# design.net
KiCad netlist of a schematic drawn in Altium Designer
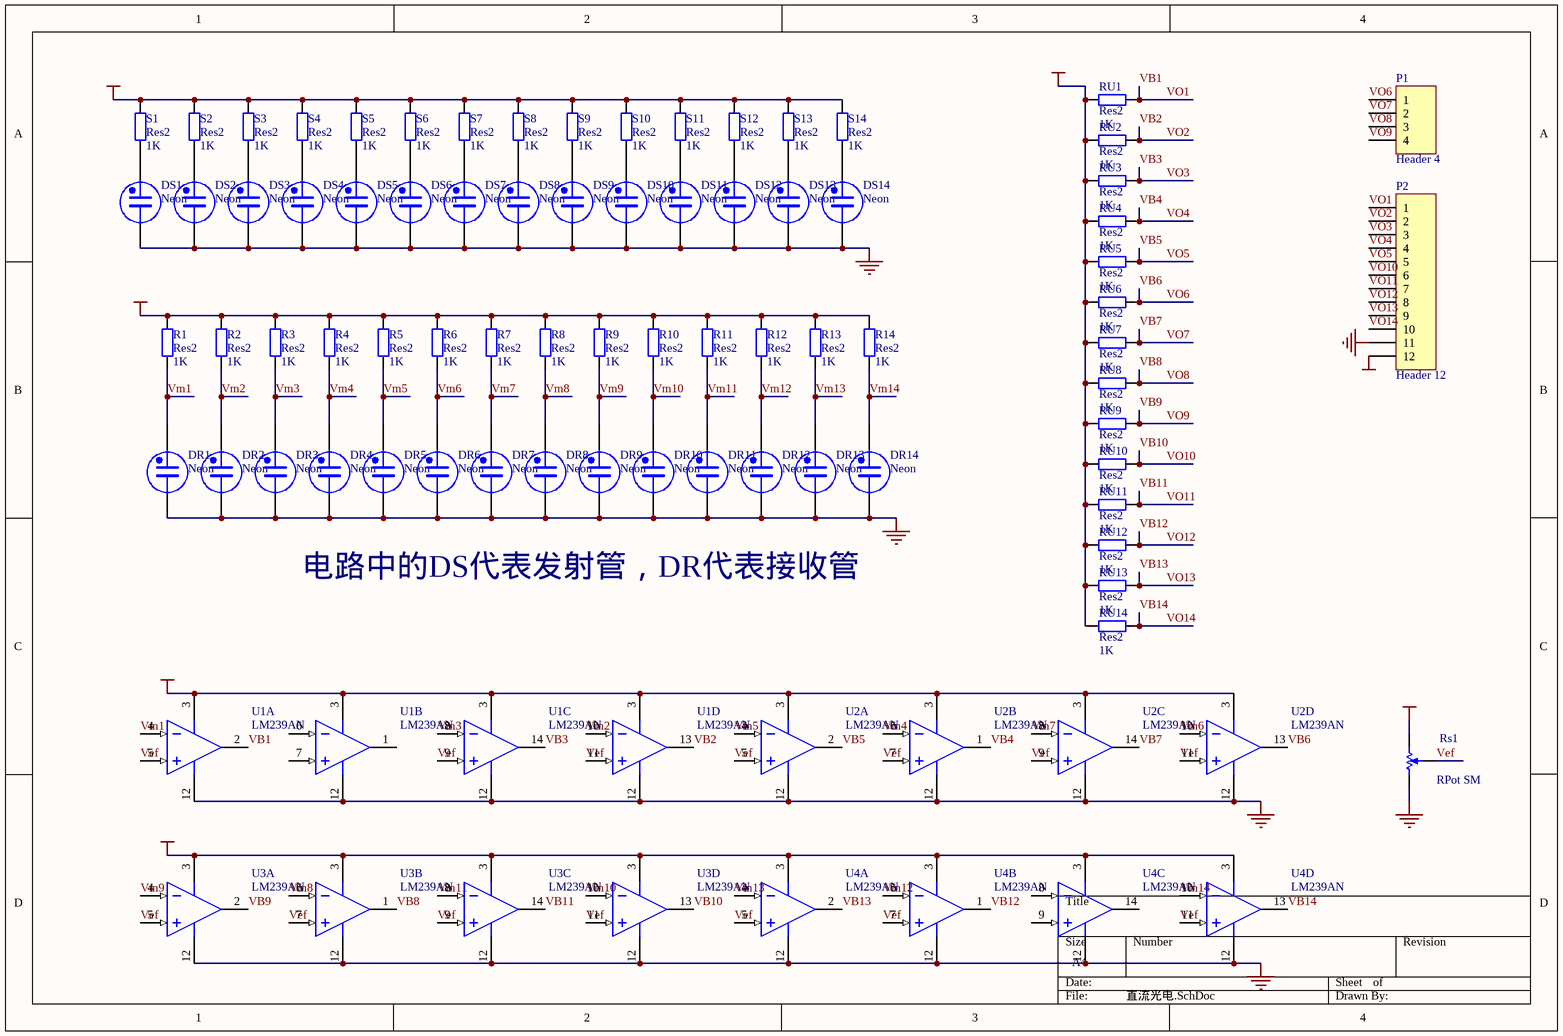
[diagram p0: 直流光电.SchDoc]

(export (version "E")
  (design (tool "Eeschema 10.0.6"))
  (components
    (comp (ref "DR1")
      (value "Neon")
      (footprint "PIN2")
      (description "Neon Bulb")
      (fields (field (name "PUBLISHER") "Altium Limited"))
      (libsource (lib "Miscellaneous Devices") (part "Neon"))
    )
    (comp (ref "DR2")
      (value "Neon")
      (footprint "PIN2")
      (description "Neon Bulb")
      (fields (field (name "PUBLISHER") "Altium Limited"))
      (libsource (lib "Miscellaneous Devices") (part "Neon"))
    )
    (comp (ref "DR3")
      (value "Neon")
      (footprint "PIN2")
      (description "Neon Bulb")
      (fields (field (name "PUBLISHER") "Altium Limited"))
      (libsource (lib "Miscellaneous Devices") (part "Neon"))
    )
    (comp (ref "DR4")
      (value "Neon")
      (footprint "PIN2")
      (description "Neon Bulb")
      (fields (field (name "PUBLISHER") "Altium Limited"))
      (libsource (lib "Miscellaneous Devices") (part "Neon"))
    )
    (comp (ref "DR5")
      (value "Neon")
      (footprint "PIN2")
      (description "Neon Bulb")
      (fields (field (name "PUBLISHER") "Altium Limited"))
      (libsource (lib "Miscellaneous Devices") (part "Neon"))
    )
    (comp (ref "DR6")
      (value "Neon")
      (footprint "PIN2")
      (description "Neon Bulb")
      (fields (field (name "PUBLISHER") "Altium Limited"))
      (libsource (lib "Miscellaneous Devices") (part "Neon"))
    )
    (comp (ref "DR7")
      (value "Neon")
      (footprint "PIN2")
      (description "Neon Bulb")
      (fields (field (name "PUBLISHER") "Altium Limited"))
      (libsource (lib "Miscellaneous Devices") (part "Neon"))
    )
    (comp (ref "DR8")
      (value "Neon")
      (footprint "PIN2")
      (description "Neon Bulb")
      (fields (field (name "PUBLISHER") "Altium Limited"))
      (libsource (lib "Miscellaneous Devices") (part "Neon"))
    )
    (comp (ref "DR9")
      (value "Neon")
      (footprint "PIN2")
      (description "Neon Bulb")
      (fields (field (name "PUBLISHER") "Altium Limited"))
      (libsource (lib "Miscellaneous Devices") (part "Neon"))
    )
    (comp (ref "DR10")
      (value "Neon")
      (footprint "PIN2")
      (description "Neon Bulb")
      (fields (field (name "PUBLISHER") "Altium Limited"))
      (libsource (lib "Miscellaneous Devices") (part "Neon"))
    )
    (comp (ref "DR11")
      (value "Neon")
      (footprint "PIN2")
      (description "Neon Bulb")
      (fields (field (name "PUBLISHER") "Altium Limited"))
      (libsource (lib "Miscellaneous Devices") (part "Neon"))
    )
    (comp (ref "DR12")
      (value "Neon")
      (footprint "PIN2")
      (description "Neon Bulb")
      (fields (field (name "PUBLISHER") "Altium Limited"))
      (libsource (lib "Miscellaneous Devices") (part "Neon"))
    )
    (comp (ref "DR13")
      (value "Neon")
      (footprint "PIN2")
      (description "Neon Bulb")
      (fields (field (name "PUBLISHER") "Altium Limited"))
      (libsource (lib "Miscellaneous Devices") (part "Neon"))
    )
    (comp (ref "DR14")
      (value "Neon")
      (footprint "PIN2")
      (description "Neon Bulb")
      (fields (field (name "PUBLISHER") "Altium Limited"))
      (libsource (lib "Miscellaneous Devices") (part "Neon"))
    )
    (comp (ref "DS1")
      (value "Neon")
      (footprint "PIN2")
      (description "Neon Bulb")
      (fields (field (name "PUBLISHER") "Altium Limited"))
      (libsource (lib "Miscellaneous Devices") (part "Neon"))
    )
    (comp (ref "DS2")
      (value "Neon")
      (footprint "PIN2")
      (description "Neon Bulb")
      (fields (field (name "PUBLISHER") "Altium Limited"))
      (libsource (lib "Miscellaneous Devices") (part "Neon"))
    )
    (comp (ref "DS3")
      (value "Neon")
      (footprint "PIN2")
      (description "Neon Bulb")
      (fields (field (name "PUBLISHER") "Altium Limited"))
      (libsource (lib "Miscellaneous Devices") (part "Neon"))
    )
    (comp (ref "DS4")
      (value "Neon")
      (footprint "PIN2")
      (description "Neon Bulb")
      (fields (field (name "PUBLISHER") "Altium Limited"))
      (libsource (lib "Miscellaneous Devices") (part "Neon"))
    )
    (comp (ref "DS5")
      (value "Neon")
      (footprint "PIN2")
      (description "Neon Bulb")
      (fields (field (name "PUBLISHER") "Altium Limited"))
      (libsource (lib "Miscellaneous Devices") (part "Neon"))
    )
    (comp (ref "DS6")
      (value "Neon")
      (footprint "PIN2")
      (description "Neon Bulb")
      (fields (field (name "PUBLISHER") "Altium Limited"))
      (libsource (lib "Miscellaneous Devices") (part "Neon"))
    )
    (comp (ref "DS7")
      (value "Neon")
      (footprint "PIN2")
      (description "Neon Bulb")
      (fields (field (name "PUBLISHER") "Altium Limited"))
      (libsource (lib "Miscellaneous Devices") (part "Neon"))
    )
    (comp (ref "DS8")
      (value "Neon")
      (footprint "PIN2")
      (description "Neon Bulb")
      (fields (field (name "PUBLISHER") "Altium Limited"))
      (libsource (lib "Miscellaneous Devices") (part "Neon"))
    )
    (comp (ref "DS9")
      (value "Neon")
      (footprint "PIN2")
      (description "Neon Bulb")
      (fields (field (name "PUBLISHER") "Altium Limited"))
      (libsource (lib "Miscellaneous Devices") (part "Neon"))
    )
    (comp (ref "DS10")
      (value "Neon")
      (footprint "PIN2")
      (description "Neon Bulb")
      (fields (field (name "PUBLISHER") "Altium Limited"))
      (libsource (lib "Miscellaneous Devices") (part "Neon"))
    )
    (comp (ref "DS11")
      (value "Neon")
      (footprint "PIN2")
      (description "Neon Bulb")
      (fields (field (name "PUBLISHER") "Altium Limited"))
      (libsource (lib "Miscellaneous Devices") (part "Neon"))
    )
    (comp (ref "DS12")
      (value "Neon")
      (footprint "PIN2")
      (description "Neon Bulb")
      (fields (field (name "PUBLISHER") "Altium Limited"))
      (libsource (lib "Miscellaneous Devices") (part "Neon"))
    )
    (comp (ref "DS13")
      (value "Neon")
      (footprint "PIN2")
      (description "Neon Bulb")
      (fields (field (name "PUBLISHER") "Altium Limited"))
      (libsource (lib "Miscellaneous Devices") (part "Neon"))
    )
    (comp (ref "DS14")
      (value "Neon")
      (footprint "PIN2")
      (description "Neon Bulb")
      (fields (field (name "PUBLISHER") "Altium Limited"))
      (libsource (lib "Miscellaneous Devices") (part "Neon"))
    )
    (comp (ref "P1")
      (value "Header 4")
      (footprint "HDR1X4")
      (description "Header, 4-Pin")
      (fields (field (name "PUBLISHER") "Altium Limited"))
      (libsource (lib "Miscellaneous Connectors") (part "Header 4"))
    )
    (comp (ref "P2")
      (value "Header 12")
      (footprint "HDR1X12")
      (description "Header, 12-Pin")
      (fields (field (name "PUBLISHER") "Altium Limited"))
      (libsource (lib "Miscellaneous Connectors") (part "Header 12"))
    )
    (comp (ref "R1")
      (value "Res2")
      (footprint "AXIAL-0.4")
      (description "Resistor")
      (fields (field (name "ALTIUM_VALUE") "1K") (field (name "PUBLISHER") "Altium Limited"))
      (libsource (lib "Miscellaneous Devices") (part "Res2"))
    )
    (comp (ref "R2")
      (value "Res2")
      (footprint "AXIAL-0.4")
      (description "Resistor")
      (fields (field (name "ALTIUM_VALUE") "1K") (field (name "PUBLISHER") "Altium Limited"))
      (libsource (lib "Miscellaneous Devices") (part "Res2"))
    )
    (comp (ref "R3")
      (value "Res2")
      (footprint "AXIAL-0.4")
      (description "Resistor")
      (fields (field (name "ALTIUM_VALUE") "1K") (field (name "PUBLISHER") "Altium Limited"))
      (libsource (lib "Miscellaneous Devices") (part "Res2"))
    )
    (comp (ref "R4")
      (value "Res2")
      (footprint "AXIAL-0.4")
      (description "Resistor")
      (fields (field (name "ALTIUM_VALUE") "1K") (field (name "PUBLISHER") "Altium Limited"))
      (libsource (lib "Miscellaneous Devices") (part "Res2"))
    )
    (comp (ref "R5")
      (value "Res2")
      (footprint "AXIAL-0.4")
      (description "Resistor")
      (fields (field (name "ALTIUM_VALUE") "1K") (field (name "PUBLISHER") "Altium Limited"))
      (libsource (lib "Miscellaneous Devices") (part "Res2"))
    )
    (comp (ref "R6")
      (value "Res2")
      (footprint "AXIAL-0.4")
      (description "Resistor")
      (fields (field (name "ALTIUM_VALUE") "1K") (field (name "PUBLISHER") "Altium Limited"))
      (libsource (lib "Miscellaneous Devices") (part "Res2"))
    )
    (comp (ref "R7")
      (value "Res2")
      (footprint "AXIAL-0.4")
      (description "Resistor")
      (fields (field (name "ALTIUM_VALUE") "1K") (field (name "PUBLISHER") "Altium Limited"))
      (libsource (lib "Miscellaneous Devices") (part "Res2"))
    )
    (comp (ref "R8")
      (value "Res2")
      (footprint "AXIAL-0.4")
      (description "Resistor")
      (fields (field (name "ALTIUM_VALUE") "1K") (field (name "PUBLISHER") "Altium Limited"))
      (libsource (lib "Miscellaneous Devices") (part "Res2"))
    )
    (comp (ref "R9")
      (value "Res2")
      (footprint "AXIAL-0.4")
      (description "Resistor")
      (fields (field (name "ALTIUM_VALUE") "1K") (field (name "PUBLISHER") "Altium Limited"))
      (libsource (lib "Miscellaneous Devices") (part "Res2"))
    )
    (comp (ref "R10")
      (value "Res2")
      (footprint "AXIAL-0.4")
      (description "Resistor")
      (fields (field (name "ALTIUM_VALUE") "1K") (field (name "PUBLISHER") "Altium Limited"))
      (libsource (lib "Miscellaneous Devices") (part "Res2"))
    )
    (comp (ref "R11")
      (value "Res2")
      (footprint "AXIAL-0.4")
      (description "Resistor")
      (fields (field (name "ALTIUM_VALUE") "1K") (field (name "PUBLISHER") "Altium Limited"))
      (libsource (lib "Miscellaneous Devices") (part "Res2"))
    )
    (comp (ref "R12")
      (value "Res2")
      (footprint "AXIAL-0.4")
      (description "Resistor")
      (fields (field (name "ALTIUM_VALUE") "1K") (field (name "PUBLISHER") "Altium Limited"))
      (libsource (lib "Miscellaneous Devices") (part "Res2"))
    )
    (comp (ref "R13")
      (value "Res2")
      (footprint "AXIAL-0.4")
      (description "Resistor")
      (fields (field (name "ALTIUM_VALUE") "1K") (field (name "PUBLISHER") "Altium Limited"))
      (libsource (lib "Miscellaneous Devices") (part "Res2"))
    )
    (comp (ref "R14")
      (value "Res2")
      (footprint "AXIAL-0.4")
      (description "Resistor")
      (fields (field (name "ALTIUM_VALUE") "1K") (field (name "PUBLISHER") "Altium Limited"))
      (libsource (lib "Miscellaneous Devices") (part "Res2"))
    )
    (comp (ref "Rs1")
      (value "RPot SM")
      (footprint "POT4MM-2")
      (description "Square Trimming Potentiometer")
      (fields (field (name "PUBLISHER") "Altium Limited"))
      (libsource (lib "Miscellaneous Devices") (part "RPot SM"))
    )
    (comp (ref "RU1")
      (value "Res2")
      (footprint "AXIAL-0.4")
      (description "Resistor")
      (fields (field (name "ALTIUM_VALUE") "1K") (field (name "PUBLISHER") "Altium Limited"))
      (libsource (lib "") (part "Res2_1"))
    )
    (comp (ref "RU2")
      (value "Res2")
      (footprint "AXIAL-0.4")
      (description "Resistor")
      (fields (field (name "ALTIUM_VALUE") "1K") (field (name "PUBLISHER") "Altium Limited"))
      (libsource (lib "") (part "Res2_1"))
    )
    (comp (ref "RU3")
      (value "Res2")
      (footprint "AXIAL-0.4")
      (description "Resistor")
      (fields (field (name "ALTIUM_VALUE") "1K") (field (name "PUBLISHER") "Altium Limited"))
      (libsource (lib "") (part "Res2_1"))
    )
    (comp (ref "RU4")
      (value "Res2")
      (footprint "AXIAL-0.4")
      (description "Resistor")
      (fields (field (name "ALTIUM_VALUE") "1K") (field (name "PUBLISHER") "Altium Limited"))
      (libsource (lib "") (part "Res2_1"))
    )
    (comp (ref "RU5")
      (value "Res2")
      (footprint "AXIAL-0.4")
      (description "Resistor")
      (fields (field (name "ALTIUM_VALUE") "1K") (field (name "PUBLISHER") "Altium Limited"))
      (libsource (lib "") (part "Res2_1"))
    )
    (comp (ref "RU6")
      (value "Res2")
      (footprint "AXIAL-0.4")
      (description "Resistor")
      (fields (field (name "ALTIUM_VALUE") "1K") (field (name "PUBLISHER") "Altium Limited"))
      (libsource (lib "") (part "Res2_1"))
    )
    (comp (ref "RU7")
      (value "Res2")
      (footprint "AXIAL-0.4")
      (description "Resistor")
      (fields (field (name "ALTIUM_VALUE") "1K") (field (name "PUBLISHER") "Altium Limited"))
      (libsource (lib "") (part "Res2_1"))
    )
    (comp (ref "RU8")
      (value "Res2")
      (footprint "AXIAL-0.4")
      (description "Resistor")
      (fields (field (name "ALTIUM_VALUE") "1K") (field (name "PUBLISHER") "Altium Limited"))
      (libsource (lib "") (part "Res2_1"))
    )
    (comp (ref "RU9")
      (value "Res2")
      (footprint "AXIAL-0.4")
      (description "Resistor")
      (fields (field (name "ALTIUM_VALUE") "1K") (field (name "PUBLISHER") "Altium Limited"))
      (libsource (lib "") (part "Res2_1"))
    )
    (comp (ref "RU10")
      (value "Res2")
      (footprint "AXIAL-0.4")
      (description "Resistor")
      (fields (field (name "ALTIUM_VALUE") "1K") (field (name "PUBLISHER") "Altium Limited"))
      (libsource (lib "") (part "Res2_1"))
    )
    (comp (ref "RU11")
      (value "Res2")
      (footprint "AXIAL-0.4")
      (description "Resistor")
      (fields (field (name "ALTIUM_VALUE") "1K") (field (name "PUBLISHER") "Altium Limited"))
      (libsource (lib "") (part "Res2_1"))
    )
    (comp (ref "RU12")
      (value "Res2")
      (footprint "AXIAL-0.4")
      (description "Resistor")
      (fields (field (name "ALTIUM_VALUE") "1K") (field (name "PUBLISHER") "Altium Limited"))
      (libsource (lib "") (part "Res2_1"))
    )
    (comp (ref "RU13")
      (value "Res2")
      (footprint "AXIAL-0.4")
      (description "Resistor")
      (fields (field (name "ALTIUM_VALUE") "1K") (field (name "PUBLISHER") "Altium Limited"))
      (libsource (lib "") (part "Res2_1"))
    )
    (comp (ref "RU14")
      (value "Res2")
      (footprint "AXIAL-0.4")
      (description "Resistor")
      (fields (field (name "ALTIUM_VALUE") "1K") (field (name "PUBLISHER") "Altium Limited"))
      (libsource (lib "") (part "Res2_1"))
    )
    (comp (ref "S1")
      (value "Res2")
      (footprint "AXIAL-0.4")
      (description "Resistor")
      (fields (field (name "ALTIUM_VALUE") "1K") (field (name "PUBLISHER") "Altium Limited"))
      (libsource (lib "Miscellaneous Devices") (part "Res2"))
    )
    (comp (ref "S2")
      (value "Res2")
      (footprint "AXIAL-0.4")
      (description "Resistor")
      (fields (field (name "ALTIUM_VALUE") "1K") (field (name "PUBLISHER") "Altium Limited"))
      (libsource (lib "Miscellaneous Devices") (part "Res2"))
    )
    (comp (ref "S3")
      (value "Res2")
      (footprint "AXIAL-0.4")
      (description "Resistor")
      (fields (field (name "ALTIUM_VALUE") "1K") (field (name "PUBLISHER") "Altium Limited"))
      (libsource (lib "Miscellaneous Devices") (part "Res2"))
    )
    (comp (ref "S4")
      (value "Res2")
      (footprint "AXIAL-0.4")
      (description "Resistor")
      (fields (field (name "ALTIUM_VALUE") "1K") (field (name "PUBLISHER") "Altium Limited"))
      (libsource (lib "Miscellaneous Devices") (part "Res2"))
    )
    (comp (ref "S5")
      (value "Res2")
      (footprint "AXIAL-0.4")
      (description "Resistor")
      (fields (field (name "ALTIUM_VALUE") "1K") (field (name "PUBLISHER") "Altium Limited"))
      (libsource (lib "Miscellaneous Devices") (part "Res2"))
    )
    (comp (ref "S6")
      (value "Res2")
      (footprint "AXIAL-0.4")
      (description "Resistor")
      (fields (field (name "ALTIUM_VALUE") "1K") (field (name "PUBLISHER") "Altium Limited"))
      (libsource (lib "Miscellaneous Devices") (part "Res2"))
    )
    (comp (ref "S7")
      (value "Res2")
      (footprint "AXIAL-0.4")
      (description "Resistor")
      (fields (field (name "ALTIUM_VALUE") "1K") (field (name "PUBLISHER") "Altium Limited"))
      (libsource (lib "Miscellaneous Devices") (part "Res2"))
    )
    (comp (ref "S8")
      (value "Res2")
      (footprint "AXIAL-0.4")
      (description "Resistor")
      (fields (field (name "ALTIUM_VALUE") "1K") (field (name "PUBLISHER") "Altium Limited"))
      (libsource (lib "Miscellaneous Devices") (part "Res2"))
    )
    (comp (ref "S9")
      (value "Res2")
      (footprint "AXIAL-0.4")
      (description "Resistor")
      (fields (field (name "ALTIUM_VALUE") "1K") (field (name "PUBLISHER") "Altium Limited"))
      (libsource (lib "Miscellaneous Devices") (part "Res2"))
    )
    (comp (ref "S10")
      (value "Res2")
      (footprint "AXIAL-0.4")
      (description "Resistor")
      (fields (field (name "ALTIUM_VALUE") "1K") (field (name "PUBLISHER") "Altium Limited"))
      (libsource (lib "Miscellaneous Devices") (part "Res2"))
    )
    (comp (ref "S11")
      (value "Res2")
      (footprint "AXIAL-0.4")
      (description "Resistor")
      (fields (field (name "ALTIUM_VALUE") "1K") (field (name "PUBLISHER") "Altium Limited"))
      (libsource (lib "Miscellaneous Devices") (part "Res2"))
    )
    (comp (ref "S12")
      (value "Res2")
      (footprint "AXIAL-0.4")
      (description "Resistor")
      (fields (field (name "ALTIUM_VALUE") "1K") (field (name "PUBLISHER") "Altium Limited"))
      (libsource (lib "Miscellaneous Devices") (part "Res2"))
    )
    (comp (ref "S13")
      (value "Res2")
      (footprint "AXIAL-0.4")
      (description "Resistor")
      (fields (field (name "ALTIUM_VALUE") "1K") (field (name "PUBLISHER") "Altium Limited"))
      (libsource (lib "Miscellaneous Devices") (part "Res2"))
    )
    (comp (ref "S14")
      (value "Res2")
      (footprint "AXIAL-0.4")
      (description "Resistor")
      (fields (field (name "ALTIUM_VALUE") "1K") (field (name "PUBLISHER") "Altium Limited"))
      (libsource (lib "Miscellaneous Devices") (part "Res2"))
    )
    (comp (ref "U1")
      (value "LM239AN")
      (footprint "DIP14")
      (description "Low-Power Quad Voltage Comparator")
      (fields (field (name "PUBLISHER") "Altium Limited"))
      (libsource (lib "ST Analog Comparator") (part "LM239AN"))
    )
    (comp (ref "U2")
      (value "LM239AN")
      (footprint "DIP14")
      (description "Low-Power Quad Voltage Comparator")
      (fields (field (name "PUBLISHER") "Altium Limited"))
      (libsource (lib "ST Analog Comparator") (part "LM239AN"))
    )
    (comp (ref "U3")
      (value "LM239AN")
      (footprint "DIP14")
      (description "Low-Power Quad Voltage Comparator")
      (fields (field (name "PUBLISHER") "Altium Limited"))
      (libsource (lib "ST Analog Comparator") (part "LM239AN"))
    )
    (comp (ref "U4")
      (value "LM239AN")
      (footprint "DIP14")
      (description "Low-Power Quad Voltage Comparator")
      (fields (field (name "PUBLISHER") "Altium Limited"))
      (libsource (lib "ST Analog Comparator") (part "LM239AN"))
    )
  )
  (nets
    (net (code "1") (name "/VB1") (class "Default")
      (node (ref "P2") (pin "1") (pinfunction "1_1") (pintype "passive"))
      (node (ref "RU1") (pin "2") (pinfunction "2_2") (pintype "passive"))
      (node (ref "U1") (pin "2") (pinfunction "OUT_2") (pintype "open_collector"))
    )
    (net (code "2") (name "/VB2") (class "Default")
      (node (ref "P2") (pin "2") (pinfunction "2_2") (pintype "passive"))
      (node (ref "RU2") (pin "2") (pinfunction "2_2") (pintype "passive"))
      (node (ref "U1") (pin "13") (pinfunction "OUT_13") (pintype "open_collector"))
    )
    (net (code "3") (name "/VB3") (class "Default")
      (node (ref "P2") (pin "3") (pinfunction "3_3") (pintype "passive"))
      (node (ref "RU3") (pin "2") (pinfunction "2_2") (pintype "passive"))
      (node (ref "U1") (pin "14") (pinfunction "OUT_14") (pintype "open_collector"))
    )
    (net (code "4") (name "/VB4") (class "Default")
      (node (ref "P2") (pin "4") (pinfunction "4_4") (pintype "passive"))
      (node (ref "RU4") (pin "2") (pinfunction "2_2") (pintype "passive"))
      (node (ref "U2") (pin "1") (pinfunction "OUT_1") (pintype "open_collector"))
    )
    (net (code "5") (name "/VB5") (class "Default")
      (node (ref "P2") (pin "5") (pinfunction "5_5") (pintype "passive"))
      (node (ref "RU5") (pin "2") (pinfunction "2_2") (pintype "passive"))
      (node (ref "U2") (pin "2") (pinfunction "OUT_2") (pintype "open_collector"))
    )
    (net (code "6") (name "/VB6") (class "Default")
      (node (ref "P1") (pin "1") (pinfunction "1_1") (pintype "passive"))
      (node (ref "RU6") (pin "2") (pinfunction "2_2") (pintype "passive"))
      (node (ref "U2") (pin "13") (pinfunction "OUT_13") (pintype "open_collector"))
    )
    (net (code "7") (name "/VB7") (class "Default")
      (node (ref "P1") (pin "2") (pinfunction "2_2") (pintype "passive"))
      (node (ref "RU7") (pin "2") (pinfunction "2_2") (pintype "passive"))
      (node (ref "U2") (pin "14") (pinfunction "OUT_14") (pintype "open_collector"))
    )
    (net (code "8") (name "/VB8") (class "Default")
      (node (ref "P1") (pin "3") (pinfunction "3_3") (pintype "passive"))
      (node (ref "RU8") (pin "2") (pinfunction "2_2") (pintype "passive"))
      (node (ref "U3") (pin "1") (pinfunction "OUT_1") (pintype "open_collector"))
    )
    (net (code "9") (name "/VB9") (class "Default")
      (node (ref "P1") (pin "4") (pinfunction "4_4") (pintype "passive"))
      (node (ref "RU9") (pin "2") (pinfunction "2_2") (pintype "passive"))
      (node (ref "U3") (pin "2") (pinfunction "OUT_2") (pintype "open_collector"))
    )
    (net (code "10") (name "/VB10") (class "Default")
      (node (ref "P2") (pin "6") (pinfunction "6_6") (pintype "passive"))
      (node (ref "RU10") (pin "2") (pinfunction "2_2") (pintype "passive"))
      (node (ref "U3") (pin "13") (pinfunction "OUT_13") (pintype "open_collector"))
    )
    (net (code "11") (name "/VB11") (class "Default")
      (node (ref "P2") (pin "7") (pinfunction "7_7") (pintype "passive"))
      (node (ref "RU11") (pin "2") (pinfunction "2_2") (pintype "passive"))
      (node (ref "U3") (pin "14") (pinfunction "OUT_14") (pintype "open_collector"))
    )
    (net (code "12") (name "/VB12") (class "Default")
      (node (ref "P2") (pin "8") (pinfunction "8_8") (pintype "passive"))
      (node (ref "RU12") (pin "2") (pinfunction "2_2") (pintype "passive"))
      (node (ref "U4") (pin "1") (pinfunction "OUT_1") (pintype "open_collector"))
    )
    (net (code "13") (name "/VB13") (class "Default")
      (node (ref "P2") (pin "9") (pinfunction "9_9") (pintype "passive"))
      (node (ref "RU13") (pin "2") (pinfunction "2_2") (pintype "passive"))
      (node (ref "U4") (pin "2") (pinfunction "OUT_2") (pintype "open_collector"))
    )
    (net (code "14") (name "/VB14") (class "Default")
      (node (ref "P2") (pin "10") (pinfunction "10_10") (pintype "passive"))
      (node (ref "RU14") (pin "2") (pinfunction "2_2") (pintype "passive"))
      (node (ref "U4") (pin "13") (pinfunction "OUT_13") (pintype "open_collector"))
    )
    (net (code "15") (name "/Vef") (class "Default")
      (node (ref "Rs1") (pin "W") (pinfunction "W_W") (pintype "passive"))
      (node (ref "U1") (pin "11") (pinfunction "IN+_11") (pintype "input"))
      (node (ref "U1") (pin "5") (pinfunction "IN+_5") (pintype "input"))
      (node (ref "U1") (pin "9") (pinfunction "IN+_9") (pintype "input"))
      (node (ref "U2") (pin "11") (pinfunction "IN+_11") (pintype "input"))
      (node (ref "U2") (pin "5") (pinfunction "IN+_5") (pintype "input"))
      (node (ref "U2") (pin "7") (pinfunction "IN+_7") (pintype "input"))
      (node (ref "U2") (pin "9") (pinfunction "IN+_9") (pintype "input"))
      (node (ref "U3") (pin "11") (pinfunction "IN+_11") (pintype "input"))
      (node (ref "U3") (pin "5") (pinfunction "IN+_5") (pintype "input"))
      (node (ref "U3") (pin "7") (pinfunction "IN+_7") (pintype "input"))
      (node (ref "U3") (pin "9") (pinfunction "IN+_9") (pintype "input"))
      (node (ref "U4") (pin "11") (pinfunction "IN+_11") (pintype "input"))
      (node (ref "U4") (pin "5") (pinfunction "IN+_5") (pintype "input"))
      (node (ref "U4") (pin "7") (pinfunction "IN+_7") (pintype "input"))
    )
    (net (code "16") (name "/Vm1") (class "Default")
      (node (ref "DR1") (pin "1") (pinfunction "1_1") (pintype "passive"))
      (node (ref "R1") (pin "1") (pinfunction "1_1") (pintype "passive"))
      (node (ref "U1") (pin "4") (pinfunction "IN-_4") (pintype "input"))
    )
    (net (code "17") (name "/Vm2") (class "Default")
      (node (ref "DR2") (pin "1") (pinfunction "1_1") (pintype "passive"))
      (node (ref "R2") (pin "1") (pinfunction "1_1") (pintype "passive"))
      (node (ref "U1") (pin "10") (pinfunction "IN-_10") (pintype "input"))
    )
    (net (code "18") (name "/Vm3") (class "Default")
      (node (ref "DR3") (pin "1") (pinfunction "1_1") (pintype "passive"))
      (node (ref "R3") (pin "1") (pinfunction "1_1") (pintype "passive"))
      (node (ref "U1") (pin "8") (pinfunction "IN-_8") (pintype "input"))
    )
    (net (code "19") (name "/Vm4") (class "Default")
      (node (ref "DR4") (pin "1") (pinfunction "1_1") (pintype "passive"))
      (node (ref "R4") (pin "1") (pinfunction "1_1") (pintype "passive"))
      (node (ref "U2") (pin "6") (pinfunction "IN-_6") (pintype "input"))
    )
    (net (code "20") (name "/Vm5") (class "Default")
      (node (ref "DR5") (pin "1") (pinfunction "1_1") (pintype "passive"))
      (node (ref "R5") (pin "1") (pinfunction "1_1") (pintype "passive"))
      (node (ref "U2") (pin "4") (pinfunction "IN-_4") (pintype "input"))
    )
    (net (code "21") (name "/Vm6") (class "Default")
      (node (ref "DR6") (pin "1") (pinfunction "1_1") (pintype "passive"))
      (node (ref "R6") (pin "1") (pinfunction "1_1") (pintype "passive"))
      (node (ref "U2") (pin "10") (pinfunction "IN-_10") (pintype "input"))
    )
    (net (code "22") (name "/Vm7") (class "Default")
      (node (ref "DR7") (pin "1") (pinfunction "1_1") (pintype "passive"))
      (node (ref "R7") (pin "1") (pinfunction "1_1") (pintype "passive"))
      (node (ref "U2") (pin "8") (pinfunction "IN-_8") (pintype "input"))
    )
    (net (code "23") (name "/Vm8") (class "Default")
      (node (ref "DR8") (pin "1") (pinfunction "1_1") (pintype "passive"))
      (node (ref "R8") (pin "1") (pinfunction "1_1") (pintype "passive"))
      (node (ref "U3") (pin "6") (pinfunction "IN-_6") (pintype "input"))
    )
    (net (code "24") (name "/Vm9") (class "Default")
      (node (ref "DR9") (pin "1") (pinfunction "1_1") (pintype "passive"))
      (node (ref "R9") (pin "1") (pinfunction "1_1") (pintype "passive"))
      (node (ref "U3") (pin "4") (pinfunction "IN-_4") (pintype "input"))
    )
    (net (code "25") (name "/Vm10") (class "Default")
      (node (ref "DR10") (pin "1") (pinfunction "1_1") (pintype "passive"))
      (node (ref "R10") (pin "1") (pinfunction "1_1") (pintype "passive"))
      (node (ref "U3") (pin "10") (pinfunction "IN-_10") (pintype "input"))
    )
    (net (code "26") (name "/Vm11") (class "Default")
      (node (ref "DR11") (pin "1") (pinfunction "1_1") (pintype "passive"))
      (node (ref "R11") (pin "1") (pinfunction "1_1") (pintype "passive"))
      (node (ref "U3") (pin "8") (pinfunction "IN-_8") (pintype "input"))
    )
    (net (code "27") (name "/Vm12") (class "Default")
      (node (ref "DR12") (pin "1") (pinfunction "1_1") (pintype "passive"))
      (node (ref "R12") (pin "1") (pinfunction "1_1") (pintype "passive"))
      (node (ref "U4") (pin "6") (pinfunction "IN-_6") (pintype "input"))
    )
    (net (code "28") (name "/Vm13") (class "Default")
      (node (ref "DR13") (pin "1") (pinfunction "1_1") (pintype "passive"))
      (node (ref "R13") (pin "1") (pinfunction "1_1") (pintype "passive"))
      (node (ref "U4") (pin "4") (pinfunction "IN-_4") (pintype "input"))
    )
    (net (code "29") (name "/Vm14") (class "Default")
      (node (ref "DR14") (pin "1") (pinfunction "1_1") (pintype "passive"))
      (node (ref "R14") (pin "1") (pinfunction "1_1") (pintype "passive"))
      (node (ref "U4") (pin "10") (pinfunction "IN-_10") (pintype "input"))
    )
    (net (code "30") (name "GND") (class "Default")
      (node (ref "DR1") (pin "2") (pinfunction "2_2") (pintype "passive"))
      (node (ref "DR10") (pin "2") (pinfunction "2_2") (pintype "passive"))
      (node (ref "DR11") (pin "2") (pinfunction "2_2") (pintype "passive"))
      (node (ref "DR12") (pin "2") (pinfunction "2_2") (pintype "passive"))
      (node (ref "DR13") (pin "2") (pinfunction "2_2") (pintype "passive"))
      (node (ref "DR14") (pin "2") (pinfunction "2_2") (pintype "passive"))
      (node (ref "DR2") (pin "2") (pinfunction "2_2") (pintype "passive"))
      (node (ref "DR3") (pin "2") (pinfunction "2_2") (pintype "passive"))
      (node (ref "DR4") (pin "2") (pinfunction "2_2") (pintype "passive"))
      (node (ref "DR5") (pin "2") (pinfunction "2_2") (pintype "passive"))
      (node (ref "DR6") (pin "2") (pinfunction "2_2") (pintype "passive"))
      (node (ref "DR7") (pin "2") (pinfunction "2_2") (pintype "passive"))
      (node (ref "DR8") (pin "2") (pinfunction "2_2") (pintype "passive"))
      (node (ref "DR9") (pin "2") (pinfunction "2_2") (pintype "passive"))
      (node (ref "DS1") (pin "2") (pinfunction "2_2") (pintype "passive"))
      (node (ref "DS10") (pin "2") (pinfunction "2_2") (pintype "passive"))
      (node (ref "DS11") (pin "2") (pinfunction "2_2") (pintype "passive"))
      (node (ref "DS12") (pin "2") (pinfunction "2_2") (pintype "passive"))
      (node (ref "DS13") (pin "2") (pinfunction "2_2") (pintype "passive"))
      (node (ref "DS14") (pin "2") (pinfunction "2_2") (pintype "passive"))
      (node (ref "DS2") (pin "2") (pinfunction "2_2") (pintype "passive"))
      (node (ref "DS3") (pin "2") (pinfunction "2_2") (pintype "passive"))
      (node (ref "DS4") (pin "2") (pinfunction "2_2") (pintype "passive"))
      (node (ref "DS5") (pin "2") (pinfunction "2_2") (pintype "passive"))
      (node (ref "DS6") (pin "2") (pinfunction "2_2") (pintype "passive"))
      (node (ref "DS7") (pin "2") (pinfunction "2_2") (pintype "passive"))
      (node (ref "DS8") (pin "2") (pinfunction "2_2") (pintype "passive"))
      (node (ref "DS9") (pin "2") (pinfunction "2_2") (pintype "passive"))
      (node (ref "P2") (pin "11") (pinfunction "11_11") (pintype "passive"))
      (node (ref "Rs1") (pin "CCW") (pinfunction "-_CCW") (pintype "passive"))
      (node (ref "U1") (pin "12") (pinfunction "V-_12") (pintype "power_in"))
      (node (ref "U2") (pin "12") (pinfunction "V-_12") (pintype "power_in"))
      (node (ref "U3") (pin "12") (pinfunction "V-_12") (pintype "power_in"))
      (node (ref "U4") (pin "12") (pinfunction "V-_12") (pintype "power_in"))
    )
    (net (code "31") (name "Net-(DS1-Pad1)") (class "Default")
      (node (ref "DS1") (pin "1") (pinfunction "1_1") (pintype "passive"))
      (node (ref "S1") (pin "1") (pinfunction "1_1") (pintype "passive"))
    )
    (net (code "32") (name "Net-(DS2-Pad1)") (class "Default")
      (node (ref "DS2") (pin "1") (pinfunction "1_1") (pintype "passive"))
      (node (ref "S2") (pin "1") (pinfunction "1_1") (pintype "passive"))
    )
    (net (code "33") (name "Net-(DS3-Pad1)") (class "Default")
      (node (ref "DS3") (pin "1") (pinfunction "1_1") (pintype "passive"))
      (node (ref "S3") (pin "1") (pinfunction "1_1") (pintype "passive"))
    )
    (net (code "34") (name "Net-(DS4-Pad1)") (class "Default")
      (node (ref "DS4") (pin "1") (pinfunction "1_1") (pintype "passive"))
      (node (ref "S4") (pin "1") (pinfunction "1_1") (pintype "passive"))
    )
    (net (code "35") (name "Net-(DS5-Pad1)") (class "Default")
      (node (ref "DS5") (pin "1") (pinfunction "1_1") (pintype "passive"))
      (node (ref "S5") (pin "1") (pinfunction "1_1") (pintype "passive"))
    )
    (net (code "36") (name "Net-(DS6-Pad1)") (class "Default")
      (node (ref "DS6") (pin "1") (pinfunction "1_1") (pintype "passive"))
      (node (ref "S6") (pin "1") (pinfunction "1_1") (pintype "passive"))
    )
    (net (code "37") (name "Net-(DS7-Pad1)") (class "Default")
      (node (ref "DS7") (pin "1") (pinfunction "1_1") (pintype "passive"))
      (node (ref "S7") (pin "1") (pinfunction "1_1") (pintype "passive"))
    )
    (net (code "38") (name "Net-(DS8-Pad1)") (class "Default")
      (node (ref "DS8") (pin "1") (pinfunction "1_1") (pintype "passive"))
      (node (ref "S8") (pin "1") (pinfunction "1_1") (pintype "passive"))
    )
    (net (code "39") (name "Net-(DS9-Pad1)") (class "Default")
      (node (ref "DS9") (pin "1") (pinfunction "1_1") (pintype "passive"))
      (node (ref "S9") (pin "1") (pinfunction "1_1") (pintype "passive"))
    )
    (net (code "40") (name "Net-(DS10-Pad1)") (class "Default")
      (node (ref "DS10") (pin "1") (pinfunction "1_1") (pintype "passive"))
      (node (ref "S10") (pin "1") (pinfunction "1_1") (pintype "passive"))
    )
    (net (code "41") (name "Net-(DS11-Pad1)") (class "Default")
      (node (ref "DS11") (pin "1") (pinfunction "1_1") (pintype "passive"))
      (node (ref "S11") (pin "1") (pinfunction "1_1") (pintype "passive"))
    )
    (net (code "42") (name "Net-(DS12-Pad1)") (class "Default")
      (node (ref "DS12") (pin "1") (pinfunction "1_1") (pintype "passive"))
      (node (ref "S12") (pin "1") (pinfunction "1_1") (pintype "passive"))
    )
    (net (code "43") (name "Net-(DS13-Pad1)") (class "Default")
      (node (ref "DS13") (pin "1") (pinfunction "1_1") (pintype "passive"))
      (node (ref "S13") (pin "1") (pinfunction "1_1") (pintype "passive"))
    )
    (net (code "44") (name "Net-(DS14-Pad1)") (class "Default")
      (node (ref "DS14") (pin "1") (pinfunction "1_1") (pintype "passive"))
      (node (ref "S14") (pin "1") (pinfunction "1_1") (pintype "passive"))
    )
    (net (code "45") (name "VCC") (class "Default")
      (node (ref "P2") (pin "12") (pinfunction "12_12") (pintype "passive"))
      (node (ref "R1") (pin "2") (pinfunction "2_2") (pintype "passive"))
      (node (ref "R10") (pin "2") (pinfunction "2_2") (pintype "passive"))
      (node (ref "R11") (pin "2") (pinfunction "2_2") (pintype "passive"))
      (node (ref "R12") (pin "2") (pinfunction "2_2") (pintype "passive"))
      (node (ref "R13") (pin "2") (pinfunction "2_2") (pintype "passive"))
      (node (ref "R14") (pin "2") (pinfunction "2_2") (pintype "passive"))
      (node (ref "R2") (pin "2") (pinfunction "2_2") (pintype "passive"))
      (node (ref "R3") (pin "2") (pinfunction "2_2") (pintype "passive"))
      (node (ref "R4") (pin "2") (pinfunction "2_2") (pintype "passive"))
      (node (ref "R5") (pin "2") (pinfunction "2_2") (pintype "passive"))
      (node (ref "R6") (pin "2") (pinfunction "2_2") (pintype "passive"))
      (node (ref "R7") (pin "2") (pinfunction "2_2") (pintype "passive"))
      (node (ref "R8") (pin "2") (pinfunction "2_2") (pintype "passive"))
      (node (ref "R9") (pin "2") (pinfunction "2_2") (pintype "passive"))
      (node (ref "RU1") (pin "1") (pinfunction "1_1") (pintype "passive"))
      (node (ref "RU10") (pin "1") (pinfunction "1_1") (pintype "passive"))
      (node (ref "RU11") (pin "1") (pinfunction "1_1") (pintype "passive"))
      (node (ref "RU12") (pin "1") (pinfunction "1_1") (pintype "passive"))
      (node (ref "RU13") (pin "1") (pinfunction "1_1") (pintype "passive"))
      (node (ref "RU14") (pin "1") (pinfunction "1_1") (pintype "passive"))
      (node (ref "RU2") (pin "1") (pinfunction "1_1") (pintype "passive"))
      (node (ref "RU3") (pin "1") (pinfunction "1_1") (pintype "passive"))
      (node (ref "RU4") (pin "1") (pinfunction "1_1") (pintype "passive"))
      (node (ref "RU5") (pin "1") (pinfunction "1_1") (pintype "passive"))
      (node (ref "RU6") (pin "1") (pinfunction "1_1") (pintype "passive"))
      (node (ref "RU7") (pin "1") (pinfunction "1_1") (pintype "passive"))
      (node (ref "RU8") (pin "1") (pinfunction "1_1") (pintype "passive"))
      (node (ref "RU9") (pin "1") (pinfunction "1_1") (pintype "passive"))
      (node (ref "Rs1") (pin "CW") (pinfunction "+_CW") (pintype "passive"))
      (node (ref "S1") (pin "2") (pinfunction "2_2") (pintype "passive"))
      (node (ref "S10") (pin "2") (pinfunction "2_2") (pintype "passive"))
      (node (ref "S11") (pin "2") (pinfunction "2_2") (pintype "passive"))
      (node (ref "S12") (pin "2") (pinfunction "2_2") (pintype "passive"))
      (node (ref "S13") (pin "2") (pinfunction "2_2") (pintype "passive"))
      (node (ref "S14") (pin "2") (pinfunction "2_2") (pintype "passive"))
      (node (ref "S2") (pin "2") (pinfunction "2_2") (pintype "passive"))
      (node (ref "S3") (pin "2") (pinfunction "2_2") (pintype "passive"))
      (node (ref "S4") (pin "2") (pinfunction "2_2") (pintype "passive"))
      (node (ref "S5") (pin "2") (pinfunction "2_2") (pintype "passive"))
      (node (ref "S6") (pin "2") (pinfunction "2_2") (pintype "passive"))
      (node (ref "S7") (pin "2") (pinfunction "2_2") (pintype "passive"))
      (node (ref "S8") (pin "2") (pinfunction "2_2") (pintype "passive"))
      (node (ref "S9") (pin "2") (pinfunction "2_2") (pintype "passive"))
      (node (ref "U1") (pin "3") (pinfunction "V+_3") (pintype "power_in"))
      (node (ref "U2") (pin "3") (pinfunction "V+_3") (pintype "power_in"))
      (node (ref "U3") (pin "3") (pinfunction "V+_3") (pintype "power_in"))
      (node (ref "U4") (pin "3") (pinfunction "V+_3") (pintype "power_in"))
    )
    (net (code "46") (name "unconnected-(U1B-IN+-Pad7)") (class "Default")
      (node (ref "U1") (pin "7") (pinfunction "IN+_7") (pintype "input"))
    )
    (net (code "47") (name "unconnected-(U1B-IN--Pad6)") (class "Default")
      (node (ref "U1") (pin "6") (pinfunction "IN-_6") (pintype "input"))
    )
    (net (code "48") (name "unconnected-(U1B-OUT-Pad1)") (class "Default")
      (node (ref "U1") (pin "1") (pinfunction "OUT_1") (pintype "open_collector"))
    )
    (net (code "49") (name "unconnected-(U4C-IN+-Pad9)") (class "Default")
      (node (ref "U4") (pin "9") (pinfunction "IN+_9") (pintype "input"))
    )
    (net (code "50") (name "unconnected-(U4C-IN--Pad8)") (class "Default")
      (node (ref "U4") (pin "8") (pinfunction "IN-_8") (pintype "input"))
    )
    (net (code "51") (name "unconnected-(U4C-OUT-Pad14)") (class "Default")
      (node (ref "U4") (pin "14") (pinfunction "OUT_14") (pintype "open_collector"))
    )
  )
)
